# matrix_mixer.net
KiCad netlist of a schematic drawn in EAGLE
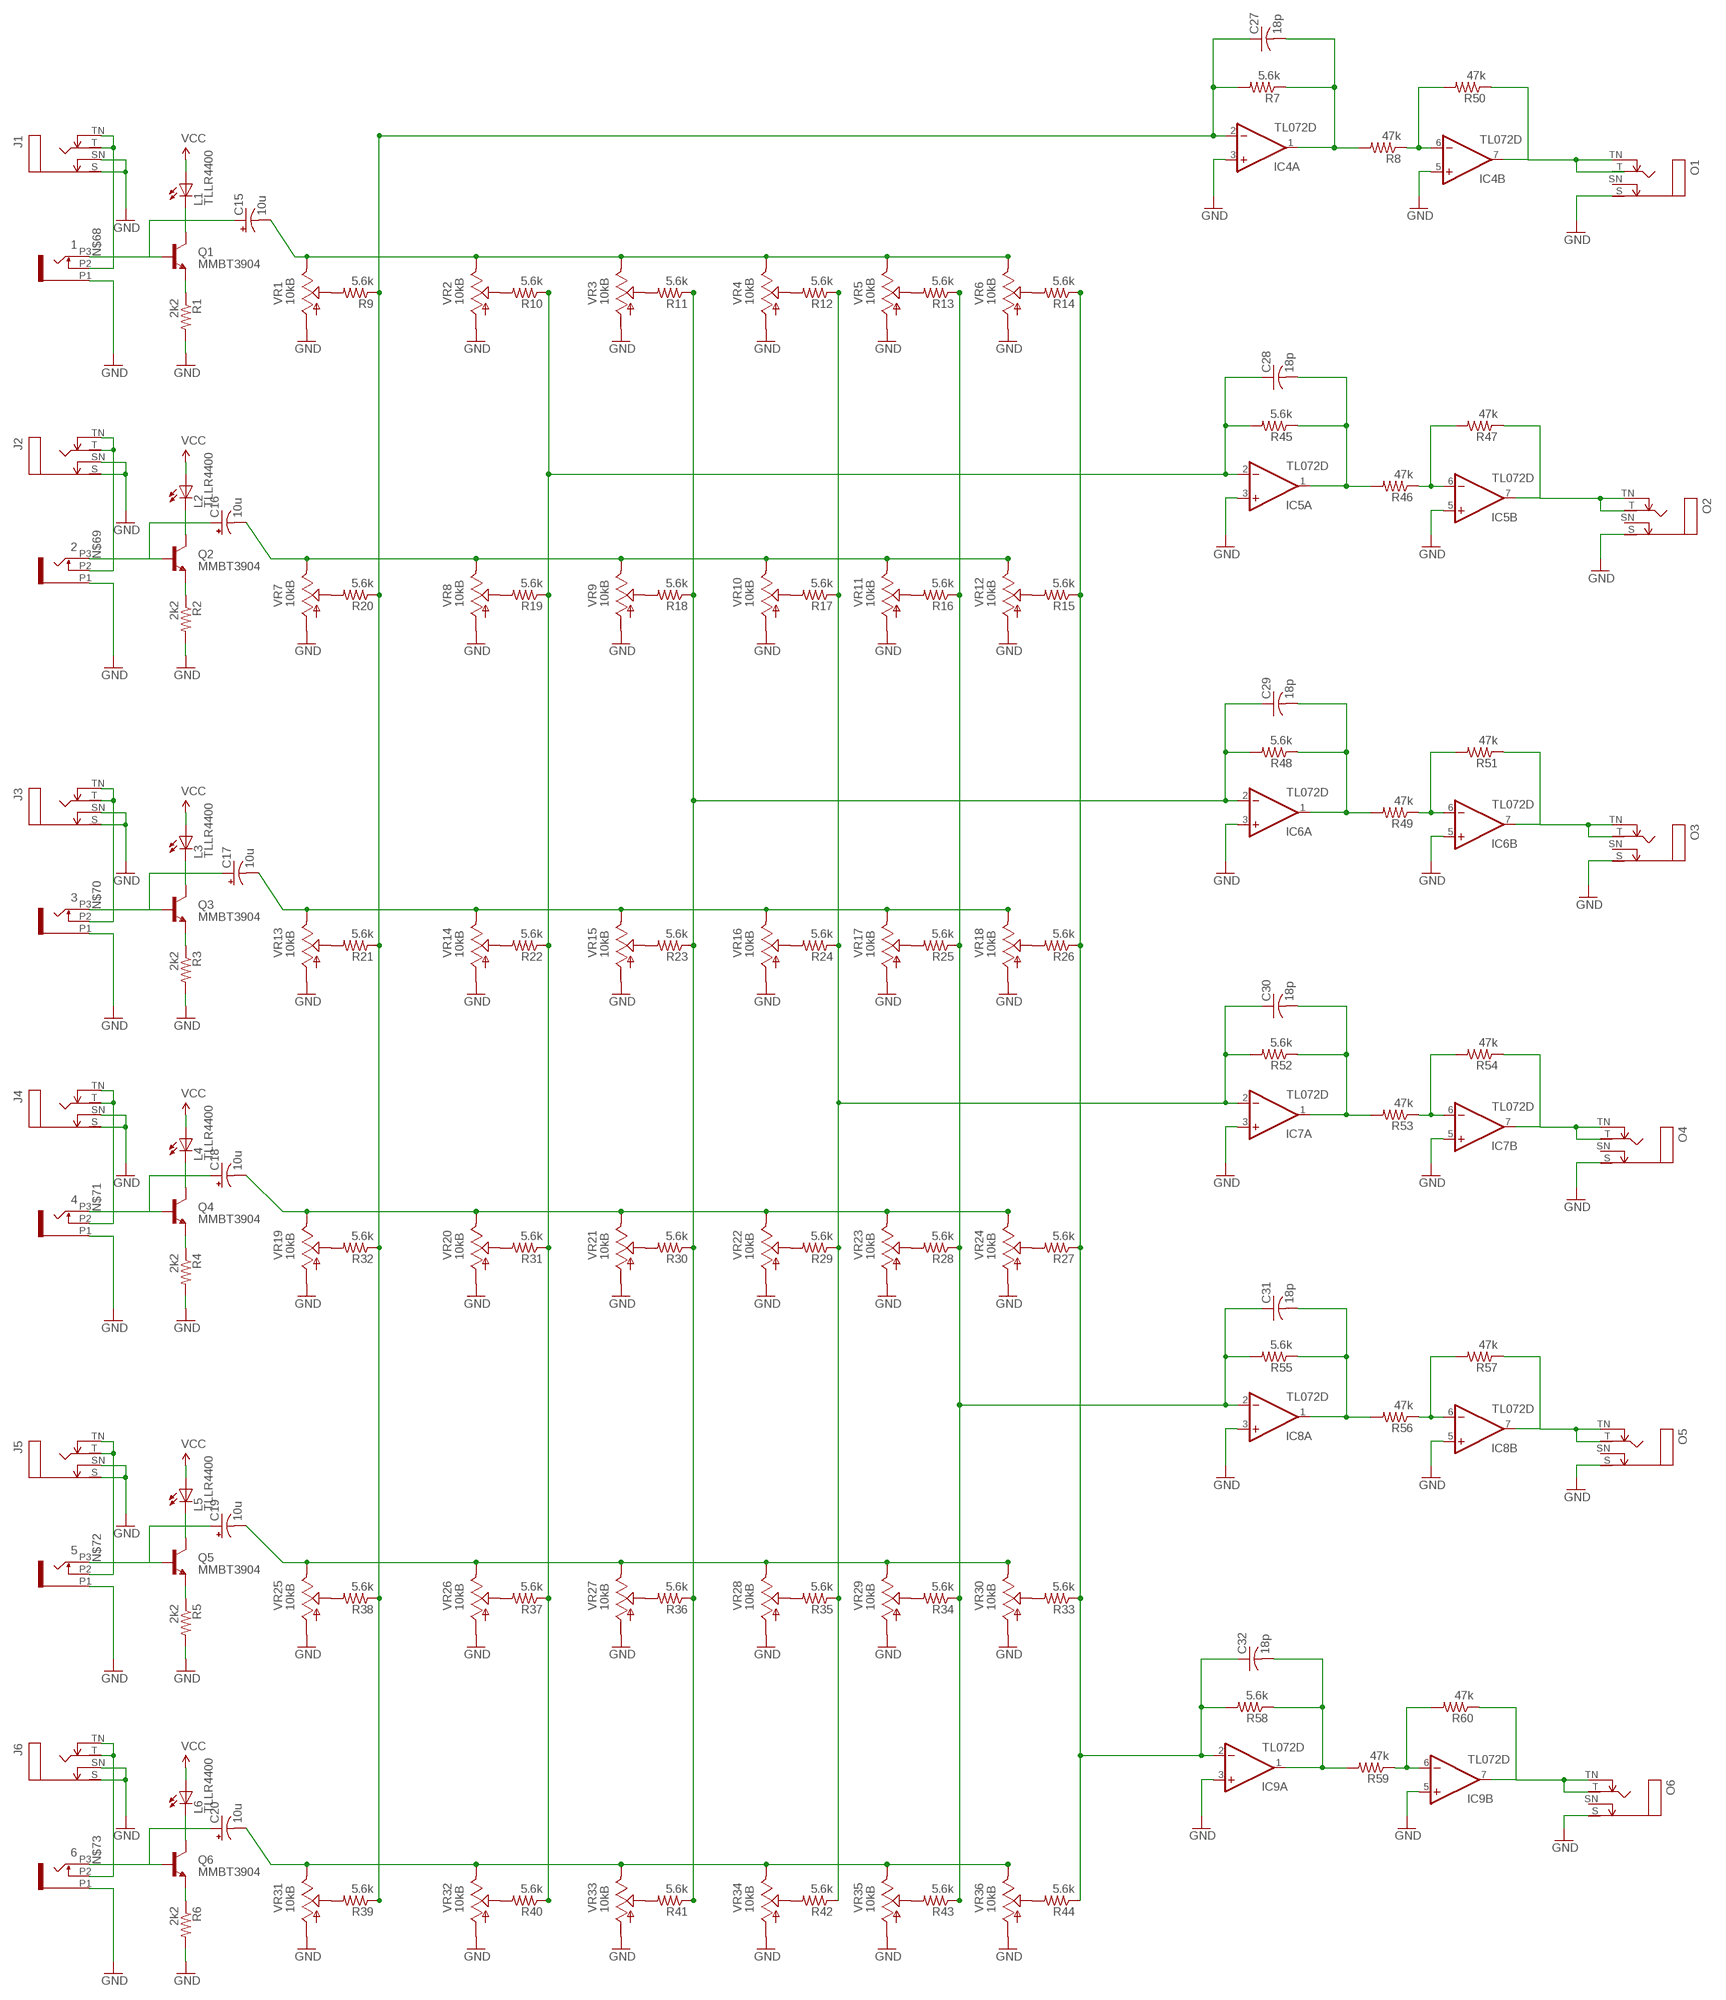
[diagram p0: schematic, sheet 1, part 1 of 2]
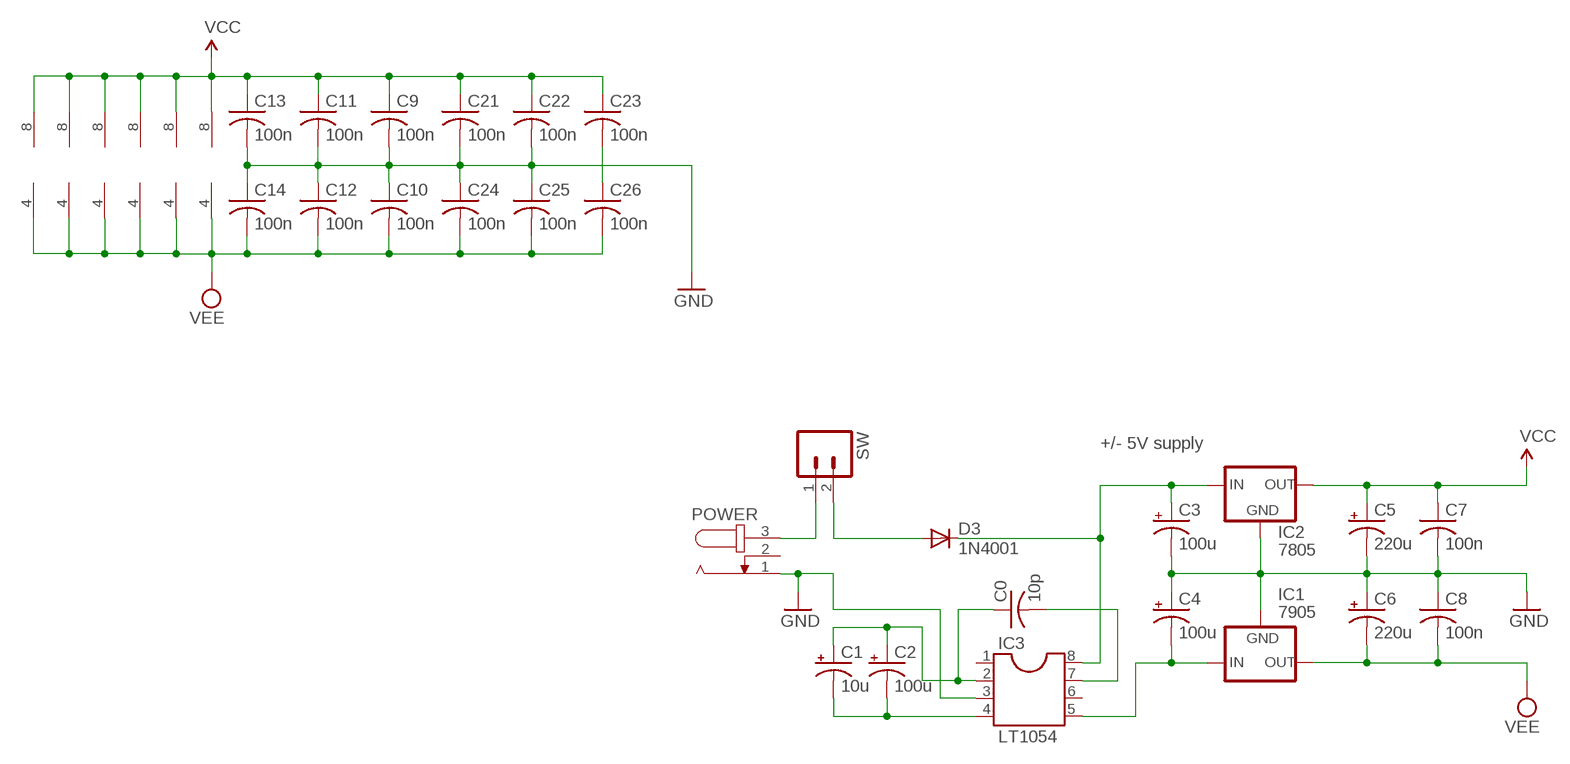
[diagram p1: schematic, sheet 1, part 2 of 2]

(export (version "E")
  (design (tool "Eeschema 10.0.6"))
  (components
    (comp (ref "1")
      (value "PJ301_THONKICONN6")
      (footprint "eagle-import:WQP_PJ_301M6")
      (libsource (lib "eagle-import") (part "PJ301_THONKICONN6"))
    )
    (comp (ref "2")
      (value "PJ301_THONKICONN6")
      (footprint "eagle-import:WQP_PJ_301M6")
      (libsource (lib "eagle-import") (part "PJ301_THONKICONN6"))
    )
    (comp (ref "3")
      (value "PJ301_THONKICONN6")
      (footprint "eagle-import:WQP_PJ_301M6")
      (libsource (lib "eagle-import") (part "PJ301_THONKICONN6"))
    )
    (comp (ref "4")
      (value "PJ301_THONKICONN6")
      (footprint "eagle-import:WQP_PJ_301M6")
      (libsource (lib "eagle-import") (part "PJ301_THONKICONN6"))
    )
    (comp (ref "5")
      (value "PJ301_THONKICONN6")
      (footprint "eagle-import:WQP_PJ_301M6")
      (libsource (lib "eagle-import") (part "PJ301_THONKICONN6"))
    )
    (comp (ref "6")
      (value "PJ301_THONKICONN6")
      (footprint "eagle-import:WQP_PJ_301M6")
      (libsource (lib "eagle-import") (part "PJ301_THONKICONN6"))
    )
    (comp (ref "C0")
      (value "10p")
      (footprint "eagle-import:C025-025X050")
      (libsource (lib "eagle-import") (part "C-US025-025X050"))
    )
    (comp (ref "C1")
      (value "10u")
      (footprint "eagle-import:E2,5-5")
      (libsource (lib "eagle-import") (part "CPOL-USE2.5-5"))
    )
    (comp (ref "C2")
      (value "100u")
      (footprint "eagle-import:E2,5-6")
      (libsource (lib "eagle-import") (part "CPOL-USE2.5-6"))
    )
    (comp (ref "C3")
      (value "100u")
      (footprint "eagle-import:E2,5-7")
      (libsource (lib "eagle-import") (part "CPOL-USE2.5-7"))
    )
    (comp (ref "C4")
      (value "100u")
      (footprint "eagle-import:E2,5-7")
      (libsource (lib "eagle-import") (part "CPOL-USE2.5-7"))
    )
    (comp (ref "C5")
      (value "220u")
      (footprint "eagle-import:E5-10,5")
      (libsource (lib "eagle-import") (part "CPOL-USE5-10.5"))
    )
    (comp (ref "C6")
      (value "220u")
      (footprint "eagle-import:E5-10,5")
      (libsource (lib "eagle-import") (part "CPOL-USE5-10.5"))
    )
    (comp (ref "C7")
      (value "100n")
      (footprint "eagle-import:C025-025X050")
      (libsource (lib "eagle-import") (part "C-US025-025X050"))
    )
    (comp (ref "C8")
      (value "100n")
      (footprint "eagle-import:C025-025X050")
      (libsource (lib "eagle-import") (part "C-US025-025X050"))
    )
    (comp (ref "C9")
      (value "100n")
      (footprint "eagle-import:C0603")
      (libsource (lib "eagle-import") (part "C-USC0603"))
    )
    (comp (ref "C10")
      (value "100n")
      (footprint "eagle-import:C0603")
      (libsource (lib "eagle-import") (part "C-USC0603"))
    )
    (comp (ref "C11")
      (value "100n")
      (footprint "eagle-import:C0603")
      (libsource (lib "eagle-import") (part "C-USC0603"))
    )
    (comp (ref "C12")
      (value "100n")
      (footprint "eagle-import:C0603")
      (libsource (lib "eagle-import") (part "C-USC0603"))
    )
    (comp (ref "C13")
      (value "100n")
      (footprint "eagle-import:C0603")
      (libsource (lib "eagle-import") (part "C-USC0603"))
    )
    (comp (ref "C14")
      (value "100n")
      (footprint "eagle-import:C0603")
      (libsource (lib "eagle-import") (part "C-USC0603"))
    )
    (comp (ref "C15")
      (value "10u")
      (footprint "eagle-import:PANASONIC_B")
      (libsource (lib "eagle-import") (part "CPOL-USB"))
    )
    (comp (ref "C16")
      (value "10u")
      (footprint "eagle-import:PANASONIC_B")
      (libsource (lib "eagle-import") (part "CPOL-USB"))
    )
    (comp (ref "C17")
      (value "10u")
      (footprint "eagle-import:PANASONIC_B")
      (libsource (lib "eagle-import") (part "CPOL-USB"))
    )
    (comp (ref "C18")
      (value "10u")
      (footprint "eagle-import:PANASONIC_B")
      (libsource (lib "eagle-import") (part "CPOL-USB"))
    )
    (comp (ref "C19")
      (value "10u")
      (footprint "eagle-import:PANASONIC_B")
      (libsource (lib "eagle-import") (part "CPOL-USB"))
    )
    (comp (ref "C20")
      (value "10u")
      (footprint "eagle-import:PANASONIC_B")
      (libsource (lib "eagle-import") (part "CPOL-USB"))
    )
    (comp (ref "C21")
      (value "100n")
      (footprint "eagle-import:C0603")
      (libsource (lib "eagle-import") (part "C-USC0603"))
    )
    (comp (ref "C22")
      (value "100n")
      (footprint "eagle-import:C0603")
      (libsource (lib "eagle-import") (part "C-USC0603"))
    )
    (comp (ref "C23")
      (value "100n")
      (footprint "eagle-import:C0603")
      (libsource (lib "eagle-import") (part "C-USC0603"))
    )
    (comp (ref "C24")
      (value "100n")
      (footprint "eagle-import:C0603")
      (libsource (lib "eagle-import") (part "C-USC0603"))
    )
    (comp (ref "C25")
      (value "100n")
      (footprint "eagle-import:C0603")
      (libsource (lib "eagle-import") (part "C-USC0603"))
    )
    (comp (ref "C26")
      (value "100n")
      (footprint "eagle-import:C0603")
      (libsource (lib "eagle-import") (part "C-USC0603"))
    )
    (comp (ref "C27")
      (value "18p")
      (footprint "eagle-import:C0603")
      (libsource (lib "eagle-import") (part "C-USC0603"))
    )
    (comp (ref "C28")
      (value "18p")
      (footprint "eagle-import:C0603")
      (libsource (lib "eagle-import") (part "C-USC0603"))
    )
    (comp (ref "C29")
      (value "18p")
      (footprint "eagle-import:C0603")
      (libsource (lib "eagle-import") (part "C-USC0603"))
    )
    (comp (ref "C30")
      (value "18p")
      (footprint "eagle-import:C0603")
      (libsource (lib "eagle-import") (part "C-USC0603"))
    )
    (comp (ref "C31")
      (value "18p")
      (footprint "eagle-import:C0603")
      (libsource (lib "eagle-import") (part "C-USC0603"))
    )
    (comp (ref "C32")
      (value "18p")
      (footprint "eagle-import:C0603")
      (libsource (lib "eagle-import") (part "C-USC0603"))
    )
    (comp (ref "D3")
      (value "1N4001")
      (footprint "eagle-import:DO41-10")
      (libsource (lib "eagle-import") (part "1N4004"))
    )
    (comp (ref "IC1")
      (value "7905")
      (footprint "eagle-import:79XXS")
      (libsource (lib "eagle-import") (part "79XXS"))
    )
    (comp (ref "IC2")
      (value "7805")
      (footprint "eagle-import:78XXS")
      (libsource (lib "eagle-import") (part "78XXS"))
    )
    (comp (ref "IC3")
      (value "LT1054")
      (footprint "eagle-import:DIL08")
      (libsource (lib "eagle-import") (part "DIL8"))
    )
    (comp (ref "IC4")
      (value "TL072D")
      (footprint "eagle-import:SO08")
      (libsource (lib "eagle-import") (part "TL072D"))
    )
    (comp (ref "IC5")
      (value "TL072D")
      (footprint "eagle-import:SO08")
      (libsource (lib "eagle-import") (part "TL072D"))
    )
    (comp (ref "IC6")
      (value "TL072D")
      (footprint "eagle-import:SO08")
      (libsource (lib "eagle-import") (part "TL072D"))
    )
    (comp (ref "IC7")
      (value "TL072D")
      (footprint "eagle-import:SO08")
      (libsource (lib "eagle-import") (part "TL072D"))
    )
    (comp (ref "IC8")
      (value "TL072D")
      (footprint "eagle-import:SO08")
      (libsource (lib "eagle-import") (part "TL072D"))
    )
    (comp (ref "IC9")
      (value "TL072D")
      (footprint "eagle-import:SO08")
      (libsource (lib "eagle-import") (part "TL072D"))
    )
    (comp (ref "J1")
      (value "MONOSWS")
      (footprint "eagle-import:NMJ4HC-S")
      (libsource (lib "eagle-import") (part "MONOSWS"))
    )
    (comp (ref "J2")
      (value "MONOSWS")
      (footprint "eagle-import:NMJ4HC-S")
      (libsource (lib "eagle-import") (part "MONOSWS"))
    )
    (comp (ref "J3")
      (value "MONOSWS")
      (footprint "eagle-import:NMJ4HC-S")
      (libsource (lib "eagle-import") (part "MONOSWS"))
    )
    (comp (ref "J4")
      (value "MONOSWS")
      (footprint "eagle-import:NMJ4HC-S")
      (libsource (lib "eagle-import") (part "MONOSWS"))
    )
    (comp (ref "J5")
      (value "MONOSWS")
      (footprint "eagle-import:NMJ4HC-S")
      (libsource (lib "eagle-import") (part "MONOSWS"))
    )
    (comp (ref "J6")
      (value "MONOSWS")
      (footprint "eagle-import:NMJ4HC-S")
      (libsource (lib "eagle-import") (part "MONOSWS"))
    )
    (comp (ref "L1")
      (value "TLLR4400")
      (footprint "eagle-import:LED3MM")
      (fields (field (name "MF") "VISHAY SEMICONDUCTOR"))
      (libsource (lib "eagle-import") (part "TLLR4400"))
    )
    (comp (ref "L2")
      (value "TLLR4400")
      (footprint "eagle-import:LED3MM")
      (fields (field (name "MF") "VISHAY SEMICONDUCTOR"))
      (libsource (lib "eagle-import") (part "TLLR4400"))
    )
    (comp (ref "L3")
      (value "TLLR4400")
      (footprint "eagle-import:LED3MM")
      (fields (field (name "MF") "VISHAY SEMICONDUCTOR"))
      (libsource (lib "eagle-import") (part "TLLR4400"))
    )
    (comp (ref "L4")
      (value "TLLR4400")
      (footprint "eagle-import:LED3MM")
      (fields (field (name "MF") "VISHAY SEMICONDUCTOR"))
      (libsource (lib "eagle-import") (part "TLLR4400"))
    )
    (comp (ref "L5")
      (value "TLLR4400")
      (footprint "eagle-import:LED3MM")
      (fields (field (name "MF") "VISHAY SEMICONDUCTOR"))
      (libsource (lib "eagle-import") (part "TLLR4400"))
    )
    (comp (ref "L6")
      (value "TLLR4400")
      (footprint "eagle-import:LED3MM")
      (fields (field (name "MF") "VISHAY SEMICONDUCTOR"))
      (libsource (lib "eagle-import") (part "TLLR4400"))
    )
    (comp (ref "O1")
      (value "MONOSWS")
      (footprint "eagle-import:NMJ4HC-S")
      (libsource (lib "eagle-import") (part "MONOSWS"))
    )
    (comp (ref "O2")
      (value "MONOSWS")
      (footprint "eagle-import:NMJ4HC-S")
      (libsource (lib "eagle-import") (part "MONOSWS"))
    )
    (comp (ref "O3")
      (value "MONOSWS")
      (footprint "eagle-import:NMJ4HC-S")
      (libsource (lib "eagle-import") (part "MONOSWS"))
    )
    (comp (ref "O4")
      (value "MONOSWS")
      (footprint "eagle-import:NMJ4HC-S")
      (libsource (lib "eagle-import") (part "MONOSWS"))
    )
    (comp (ref "O5")
      (value "MONOSWS")
      (footprint "eagle-import:NMJ4HC-S")
      (libsource (lib "eagle-import") (part "MONOSWS"))
    )
    (comp (ref "O6")
      (value "MONOSWS")
      (footprint "eagle-import:NMJ4HC-S")
      (libsource (lib "eagle-import") (part "MONOSWS"))
    )
    (comp (ref "POWER")
      (value "JACK-PLUG2")
      (footprint "eagle-import:SPC4078_BIG_HOLES")
      (libsource (lib "eagle-import") (part "JACK-PLUG2"))
    )
    (comp (ref "Q1")
      (value "MMBT3904")
      (footprint "eagle-import:SOT23-BEC")
      (libsource (lib "eagle-import") (part "-NPN-SOT23-BECMMBT3904LT1"))
    )
    (comp (ref "Q2")
      (value "MMBT3904")
      (footprint "eagle-import:SOT23-BEC")
      (libsource (lib "eagle-import") (part "-NPN-SOT23-BECMMBT3904LT1"))
    )
    (comp (ref "Q3")
      (value "MMBT3904")
      (footprint "eagle-import:SOT23-BEC")
      (libsource (lib "eagle-import") (part "-NPN-SOT23-BECMMBT3904LT1"))
    )
    (comp (ref "Q4")
      (value "MMBT3904")
      (footprint "eagle-import:SOT23-BEC")
      (libsource (lib "eagle-import") (part "-NPN-SOT23-BECMMBT3904LT1"))
    )
    (comp (ref "Q5")
      (value "MMBT3904")
      (footprint "eagle-import:SOT23-BEC")
      (libsource (lib "eagle-import") (part "-NPN-SOT23-BECMMBT3904LT1"))
    )
    (comp (ref "Q6")
      (value "MMBT3904")
      (footprint "eagle-import:SOT23-BEC")
      (libsource (lib "eagle-import") (part "-NPN-SOT23-BECMMBT3904LT1"))
    )
    (comp (ref "R1")
      (value "2k2")
      (footprint "eagle-import:R0603")
      (libsource (lib "eagle-import") (part "R-US_R0603"))
    )
    (comp (ref "R2")
      (value "2k2")
      (footprint "eagle-import:R0603")
      (libsource (lib "eagle-import") (part "R-US_R0603"))
    )
    (comp (ref "R3")
      (value "2k2")
      (footprint "eagle-import:R0603")
      (libsource (lib "eagle-import") (part "R-US_R0603"))
    )
    (comp (ref "R4")
      (value "2k2")
      (footprint "eagle-import:R0603")
      (libsource (lib "eagle-import") (part "R-US_R0603"))
    )
    (comp (ref "R5")
      (value "2k2")
      (footprint "eagle-import:R0603")
      (libsource (lib "eagle-import") (part "R-US_R0603"))
    )
    (comp (ref "R6")
      (value "2k2")
      (footprint "eagle-import:R0603")
      (libsource (lib "eagle-import") (part "R-US_R0603"))
    )
    (comp (ref "R7")
      (value "5.6k")
      (footprint "eagle-import:R0603")
      (libsource (lib "eagle-import") (part "R-US_R0603"))
    )
    (comp (ref "R8")
      (value "47k")
      (footprint "eagle-import:R0603")
      (libsource (lib "eagle-import") (part "R-US_R0603"))
    )
    (comp (ref "R9")
      (value "5.6k")
      (footprint "eagle-import:R0603")
      (libsource (lib "eagle-import") (part "R-US_R0603"))
    )
    (comp (ref "R10")
      (value "5.6k")
      (footprint "eagle-import:R0603")
      (libsource (lib "eagle-import") (part "R-US_R0603"))
    )
    (comp (ref "R11")
      (value "5.6k")
      (footprint "eagle-import:R0603")
      (libsource (lib "eagle-import") (part "R-US_R0603"))
    )
    (comp (ref "R12")
      (value "5.6k")
      (footprint "eagle-import:R0603")
      (libsource (lib "eagle-import") (part "R-US_R0603"))
    )
    (comp (ref "R13")
      (value "5.6k")
      (footprint "eagle-import:R0603")
      (libsource (lib "eagle-import") (part "R-US_R0603"))
    )
    (comp (ref "R14")
      (value "5.6k")
      (footprint "eagle-import:R0603")
      (libsource (lib "eagle-import") (part "R-US_R0603"))
    )
    (comp (ref "R15")
      (value "5.6k")
      (footprint "eagle-import:R0603")
      (libsource (lib "eagle-import") (part "R-US_R0603"))
    )
    (comp (ref "R16")
      (value "5.6k")
      (footprint "eagle-import:R0603")
      (libsource (lib "eagle-import") (part "R-US_R0603"))
    )
    (comp (ref "R17")
      (value "5.6k")
      (footprint "eagle-import:R0603")
      (libsource (lib "eagle-import") (part "R-US_R0603"))
    )
    (comp (ref "R18")
      (value "5.6k")
      (footprint "eagle-import:R0603")
      (libsource (lib "eagle-import") (part "R-US_R0603"))
    )
    (comp (ref "R19")
      (value "5.6k")
      (footprint "eagle-import:R0603")
      (libsource (lib "eagle-import") (part "R-US_R0603"))
    )
    (comp (ref "R20")
      (value "5.6k")
      (footprint "eagle-import:R0603")
      (libsource (lib "eagle-import") (part "R-US_R0603"))
    )
    (comp (ref "R21")
      (value "5.6k")
      (footprint "eagle-import:R0603")
      (libsource (lib "eagle-import") (part "R-US_R0603"))
    )
    (comp (ref "R22")
      (value "5.6k")
      (footprint "eagle-import:R0603")
      (libsource (lib "eagle-import") (part "R-US_R0603"))
    )
    (comp (ref "R23")
      (value "5.6k")
      (footprint "eagle-import:R0603")
      (libsource (lib "eagle-import") (part "R-US_R0603"))
    )
    (comp (ref "R24")
      (value "5.6k")
      (footprint "eagle-import:R0603")
      (libsource (lib "eagle-import") (part "R-US_R0603"))
    )
    (comp (ref "R25")
      (value "5.6k")
      (footprint "eagle-import:R0603")
      (libsource (lib "eagle-import") (part "R-US_R0603"))
    )
    (comp (ref "R26")
      (value "5.6k")
      (footprint "eagle-import:R0603")
      (libsource (lib "eagle-import") (part "R-US_R0603"))
    )
    (comp (ref "R27")
      (value "5.6k")
      (footprint "eagle-import:R0603")
      (libsource (lib "eagle-import") (part "R-US_R0603"))
    )
    (comp (ref "R28")
      (value "5.6k")
      (footprint "eagle-import:R0603")
      (libsource (lib "eagle-import") (part "R-US_R0603"))
    )
    (comp (ref "R29")
      (value "5.6k")
      (footprint "eagle-import:R0603")
      (libsource (lib "eagle-import") (part "R-US_R0603"))
    )
    (comp (ref "R30")
      (value "5.6k")
      (footprint "eagle-import:R0603")
      (libsource (lib "eagle-import") (part "R-US_R0603"))
    )
    (comp (ref "R31")
      (value "5.6k")
      (footprint "eagle-import:R0603")
      (libsource (lib "eagle-import") (part "R-US_R0603"))
    )
    (comp (ref "R32")
      (value "5.6k")
      (footprint "eagle-import:R0603")
      (libsource (lib "eagle-import") (part "R-US_R0603"))
    )
    (comp (ref "R33")
      (value "5.6k")
      (footprint "eagle-import:R0603")
      (libsource (lib "eagle-import") (part "R-US_R0603"))
    )
    (comp (ref "R34")
      (value "5.6k")
      (footprint "eagle-import:R0603")
      (libsource (lib "eagle-import") (part "R-US_R0603"))
    )
    (comp (ref "R35")
      (value "5.6k")
      (footprint "eagle-import:R0603")
      (libsource (lib "eagle-import") (part "R-US_R0603"))
    )
    (comp (ref "R36")
      (value "5.6k")
      (footprint "eagle-import:R0603")
      (libsource (lib "eagle-import") (part "R-US_R0603"))
    )
    (comp (ref "R37")
      (value "5.6k")
      (footprint "eagle-import:R0603")
      (libsource (lib "eagle-import") (part "R-US_R0603"))
    )
    (comp (ref "R38")
      (value "5.6k")
      (footprint "eagle-import:R0603")
      (libsource (lib "eagle-import") (part "R-US_R0603"))
    )
    (comp (ref "R39")
      (value "5.6k")
      (footprint "eagle-import:R0603")
      (libsource (lib "eagle-import") (part "R-US_R0603"))
    )
    (comp (ref "R40")
      (value "5.6k")
      (footprint "eagle-import:R0603")
      (libsource (lib "eagle-import") (part "R-US_R0603"))
    )
    (comp (ref "R41")
      (value "5.6k")
      (footprint "eagle-import:R0603")
      (libsource (lib "eagle-import") (part "R-US_R0603"))
    )
    (comp (ref "R42")
      (value "5.6k")
      (footprint "eagle-import:R0603")
      (libsource (lib "eagle-import") (part "R-US_R0603"))
    )
    (comp (ref "R43")
      (value "5.6k")
      (footprint "eagle-import:R0603")
      (libsource (lib "eagle-import") (part "R-US_R0603"))
    )
    (comp (ref "R44")
      (value "5.6k")
      (footprint "eagle-import:R0603")
      (libsource (lib "eagle-import") (part "R-US_R0603"))
    )
    (comp (ref "R45")
      (value "5.6k")
      (footprint "eagle-import:R0603")
      (libsource (lib "eagle-import") (part "R-US_R0603"))
    )
    (comp (ref "R46")
      (value "47k")
      (footprint "eagle-import:R0603")
      (libsource (lib "eagle-import") (part "R-US_R0603"))
    )
    (comp (ref "R47")
      (value "47k")
      (footprint "eagle-import:R0603")
      (libsource (lib "eagle-import") (part "R-US_R0603"))
    )
    (comp (ref "R48")
      (value "5.6k")
      (footprint "eagle-import:R0603")
      (libsource (lib "eagle-import") (part "R-US_R0603"))
    )
    (comp (ref "R49")
      (value "47k")
      (footprint "eagle-import:R0603")
      (libsource (lib "eagle-import") (part "R-US_R0603"))
    )
    (comp (ref "R50")
      (value "47k")
      (footprint "eagle-import:R0603")
      (libsource (lib "eagle-import") (part "R-US_R0603"))
    )
    (comp (ref "R51")
      (value "47k")
      (footprint "eagle-import:R0603")
      (libsource (lib "eagle-import") (part "R-US_R0603"))
    )
    (comp (ref "R52")
      (value "5.6k")
      (footprint "eagle-import:R0603")
      (libsource (lib "eagle-import") (part "R-US_R0603"))
    )
    (comp (ref "R53")
      (value "47k")
      (footprint "eagle-import:R0603")
      (libsource (lib "eagle-import") (part "R-US_R0603"))
    )
    (comp (ref "R54")
      (value "47k")
      (footprint "eagle-import:R0603")
      (libsource (lib "eagle-import") (part "R-US_R0603"))
    )
    (comp (ref "R55")
      (value "5.6k")
      (footprint "eagle-import:R0603")
      (libsource (lib "eagle-import") (part "R-US_R0603"))
    )
    (comp (ref "R56")
      (value "47k")
      (footprint "eagle-import:R0603")
      (libsource (lib "eagle-import") (part "R-US_R0603"))
    )
    (comp (ref "R57")
      (value "47k")
      (footprint "eagle-import:R0603")
      (libsource (lib "eagle-import") (part "R-US_R0603"))
    )
    (comp (ref "R58")
      (value "5.6k")
      (footprint "eagle-import:R0603")
      (libsource (lib "eagle-import") (part "R-US_R0603"))
    )
    (comp (ref "R59")
      (value "47k")
      (footprint "eagle-import:R0603")
      (libsource (lib "eagle-import") (part "R-US_R0603"))
    )
    (comp (ref "R60")
      (value "47k")
      (footprint "eagle-import:R0603")
      (libsource (lib "eagle-import") (part "R-US_R0603"))
    )
    (comp (ref "SW")
      (value "M02PTH")
      (footprint "eagle-import:1X02")
      (libsource (lib "eagle-import") (part "M02PTH"))
    )
    (comp (ref "VR1")
      (value "10kB")
      (footprint "eagle-import:ALPS_POT_VERTICAL_PS")
      (libsource (lib "eagle-import") (part "POT_USVERTICAL_PS"))
    )
    (comp (ref "VR2")
      (value "10kB")
      (footprint "eagle-import:ALPS_POT_VERTICAL_PS")
      (libsource (lib "eagle-import") (part "POT_USVERTICAL_PS"))
    )
    (comp (ref "VR3")
      (value "10kB")
      (footprint "eagle-import:ALPS_POT_VERTICAL_PS")
      (libsource (lib "eagle-import") (part "POT_USVERTICAL_PS"))
    )
    (comp (ref "VR4")
      (value "10kB")
      (footprint "eagle-import:ALPS_POT_VERTICAL_PS")
      (libsource (lib "eagle-import") (part "POT_USVERTICAL_PS"))
    )
    (comp (ref "VR5")
      (value "10kB")
      (footprint "eagle-import:ALPS_POT_VERTICAL_PS")
      (libsource (lib "eagle-import") (part "POT_USVERTICAL_PS"))
    )
    (comp (ref "VR6")
      (value "10kB")
      (footprint "eagle-import:ALPS_POT_VERTICAL_PS")
      (libsource (lib "eagle-import") (part "POT_USVERTICAL_PS"))
    )
    (comp (ref "VR7")
      (value "10kB")
      (footprint "eagle-import:ALPS_POT_VERTICAL_PS")
      (libsource (lib "eagle-import") (part "POT_USVERTICAL_PS"))
    )
    (comp (ref "VR8")
      (value "10kB")
      (footprint "eagle-import:ALPS_POT_VERTICAL_PS")
      (libsource (lib "eagle-import") (part "POT_USVERTICAL_PS"))
    )
    (comp (ref "VR9")
      (value "10kB")
      (footprint "eagle-import:ALPS_POT_VERTICAL_PS")
      (libsource (lib "eagle-import") (part "POT_USVERTICAL_PS"))
    )
    (comp (ref "VR10")
      (value "10kB")
      (footprint "eagle-import:ALPS_POT_VERTICAL_PS")
      (libsource (lib "eagle-import") (part "POT_USVERTICAL_PS"))
    )
    (comp (ref "VR11")
      (value "10kB")
      (footprint "eagle-import:ALPS_POT_VERTICAL_PS")
      (libsource (lib "eagle-import") (part "POT_USVERTICAL_PS"))
    )
    (comp (ref "VR12")
      (value "10kB")
      (footprint "eagle-import:ALPS_POT_VERTICAL_PS")
      (libsource (lib "eagle-import") (part "POT_USVERTICAL_PS"))
    )
    (comp (ref "VR13")
      (value "10kB")
      (footprint "eagle-import:ALPS_POT_VERTICAL_PS")
      (libsource (lib "eagle-import") (part "POT_USVERTICAL_PS"))
    )
    (comp (ref "VR14")
      (value "10kB")
      (footprint "eagle-import:ALPS_POT_VERTICAL_PS")
      (libsource (lib "eagle-import") (part "POT_USVERTICAL_PS"))
    )
    (comp (ref "VR15")
      (value "10kB")
      (footprint "eagle-import:ALPS_POT_VERTICAL_PS")
      (libsource (lib "eagle-import") (part "POT_USVERTICAL_PS"))
    )
    (comp (ref "VR16")
      (value "10kB")
      (footprint "eagle-import:ALPS_POT_VERTICAL_PS")
      (libsource (lib "eagle-import") (part "POT_USVERTICAL_PS"))
    )
    (comp (ref "VR17")
      (value "10kB")
      (footprint "eagle-import:ALPS_POT_VERTICAL_PS")
      (libsource (lib "eagle-import") (part "POT_USVERTICAL_PS"))
    )
    (comp (ref "VR18")
      (value "10kB")
      (footprint "eagle-import:ALPS_POT_VERTICAL_PS")
      (libsource (lib "eagle-import") (part "POT_USVERTICAL_PS"))
    )
    (comp (ref "VR19")
      (value "10kB")
      (footprint "eagle-import:ALPS_POT_VERTICAL_PS")
      (libsource (lib "eagle-import") (part "POT_USVERTICAL_PS"))
    )
    (comp (ref "VR20")
      (value "10kB")
      (footprint "eagle-import:ALPS_POT_VERTICAL_PS")
      (libsource (lib "eagle-import") (part "POT_USVERTICAL_PS"))
    )
    (comp (ref "VR21")
      (value "10kB")
      (footprint "eagle-import:ALPS_POT_VERTICAL_PS")
      (libsource (lib "eagle-import") (part "POT_USVERTICAL_PS"))
    )
    (comp (ref "VR22")
      (value "10kB")
      (footprint "eagle-import:ALPS_POT_VERTICAL_PS")
      (libsource (lib "eagle-import") (part "POT_USVERTICAL_PS"))
    )
    (comp (ref "VR23")
      (value "10kB")
      (footprint "eagle-import:ALPS_POT_VERTICAL_PS")
      (libsource (lib "eagle-import") (part "POT_USVERTICAL_PS"))
    )
    (comp (ref "VR24")
      (value "10kB")
      (footprint "eagle-import:ALPS_POT_VERTICAL_PS")
      (libsource (lib "eagle-import") (part "POT_USVERTICAL_PS"))
    )
    (comp (ref "VR25")
      (value "10kB")
      (footprint "eagle-import:ALPS_POT_VERTICAL_PS")
      (libsource (lib "eagle-import") (part "POT_USVERTICAL_PS"))
    )
    (comp (ref "VR26")
      (value "10kB")
      (footprint "eagle-import:ALPS_POT_VERTICAL_PS")
      (libsource (lib "eagle-import") (part "POT_USVERTICAL_PS"))
    )
    (comp (ref "VR27")
      (value "10kB")
      (footprint "eagle-import:ALPS_POT_VERTICAL_PS")
      (libsource (lib "eagle-import") (part "POT_USVERTICAL_PS"))
    )
    (comp (ref "VR28")
      (value "10kB")
      (footprint "eagle-import:ALPS_POT_VERTICAL_PS")
      (libsource (lib "eagle-import") (part "POT_USVERTICAL_PS"))
    )
    (comp (ref "VR29")
      (value "10kB")
      (footprint "eagle-import:ALPS_POT_VERTICAL_PS")
      (libsource (lib "eagle-import") (part "POT_USVERTICAL_PS"))
    )
    (comp (ref "VR30")
      (value "10kB")
      (footprint "eagle-import:ALPS_POT_VERTICAL_PS")
      (libsource (lib "eagle-import") (part "POT_USVERTICAL_PS"))
    )
    (comp (ref "VR31")
      (value "10kB")
      (footprint "eagle-import:ALPS_POT_VERTICAL_PS")
      (libsource (lib "eagle-import") (part "POT_USVERTICAL_PS"))
    )
    (comp (ref "VR32")
      (value "10kB")
      (footprint "eagle-import:ALPS_POT_VERTICAL_PS")
      (libsource (lib "eagle-import") (part "POT_USVERTICAL_PS"))
    )
    (comp (ref "VR33")
      (value "10kB")
      (footprint "eagle-import:ALPS_POT_VERTICAL_PS")
      (libsource (lib "eagle-import") (part "POT_USVERTICAL_PS"))
    )
    (comp (ref "VR34")
      (value "10kB")
      (footprint "eagle-import:ALPS_POT_VERTICAL_PS")
      (libsource (lib "eagle-import") (part "POT_USVERTICAL_PS"))
    )
    (comp (ref "VR35")
      (value "10kB")
      (footprint "eagle-import:ALPS_POT_VERTICAL_PS")
      (libsource (lib "eagle-import") (part "POT_USVERTICAL_PS"))
    )
    (comp (ref "VR36")
      (value "10kB")
      (footprint "eagle-import:ALPS_POT_VERTICAL_PS")
      (libsource (lib "eagle-import") (part "POT_USVERTICAL_PS"))
    )
  )
  (nets
    (net (code "1") (name "/N$68") (class "Default")
      (node (ref "1") (pin "P3") (pinfunction "3_P3") (pintype "passive"))
      (node (ref "C15") (pin "+") (pinfunction "+_+") (pintype "passive"))
      (node (ref "Q1") (pin "B") (pinfunction "B_B") (pintype "passive"))
    )
    (net (code "2") (name "/N$69") (class "Default")
      (node (ref "2") (pin "P3") (pinfunction "3_P3") (pintype "passive"))
      (node (ref "C16") (pin "+") (pinfunction "+_+") (pintype "passive"))
      (node (ref "Q2") (pin "B") (pinfunction "B_B") (pintype "passive"))
    )
    (net (code "3") (name "/N$70") (class "Default")
      (node (ref "3") (pin "P3") (pinfunction "3_P3") (pintype "passive"))
      (node (ref "C17") (pin "+") (pinfunction "+_+") (pintype "passive"))
      (node (ref "Q3") (pin "B") (pinfunction "B_B") (pintype "passive"))
    )
    (net (code "4") (name "/N$71") (class "Default")
      (node (ref "4") (pin "P3") (pinfunction "3_P3") (pintype "passive"))
      (node (ref "C18") (pin "+") (pinfunction "+_+") (pintype "passive"))
      (node (ref "Q4") (pin "B") (pinfunction "B_B") (pintype "passive"))
    )
    (net (code "5") (name "/N$72") (class "Default")
      (node (ref "5") (pin "P3") (pinfunction "3_P3") (pintype "passive"))
      (node (ref "C19") (pin "+") (pinfunction "+_+") (pintype "passive"))
      (node (ref "Q5") (pin "B") (pinfunction "B_B") (pintype "passive"))
    )
    (net (code "6") (name "/N$73") (class "Default")
      (node (ref "6") (pin "P3") (pinfunction "3_P3") (pintype "passive"))
      (node (ref "C20") (pin "+") (pinfunction "+_+") (pintype "passive"))
      (node (ref "Q6") (pin "B") (pinfunction "B_B") (pintype "passive"))
    )
    (net (code "7") (name "GND") (class "Default")
      (node (ref "1") (pin "P1") (pinfunction "1_P1") (pintype "passive"))
      (node (ref "2") (pin "P1") (pinfunction "1_P1") (pintype "passive"))
      (node (ref "3") (pin "P1") (pinfunction "1_P1") (pintype "passive"))
      (node (ref "4") (pin "P1") (pinfunction "1_P1") (pintype "passive"))
      (node (ref "5") (pin "P1") (pinfunction "1_P1") (pintype "passive"))
      (node (ref "6") (pin "P1") (pinfunction "1_P1") (pintype "passive"))
      (node (ref "C10") (pin "1") (pinfunction "1_1") (pintype "passive"))
      (node (ref "C11") (pin "2") (pinfunction "2_2") (pintype "passive"))
      (node (ref "C12") (pin "1") (pinfunction "1_1") (pintype "passive"))
      (node (ref "C13") (pin "2") (pinfunction "2_2") (pintype "passive"))
      (node (ref "C14") (pin "1") (pinfunction "1_1") (pintype "passive"))
      (node (ref "C21") (pin "2") (pinfunction "2_2") (pintype "passive"))
      (node (ref "C22") (pin "2") (pinfunction "2_2") (pintype "passive"))
      (node (ref "C23") (pin "2") (pinfunction "2_2") (pintype "passive"))
      (node (ref "C24") (pin "1") (pinfunction "1_1") (pintype "passive"))
      (node (ref "C25") (pin "1") (pinfunction "1_1") (pintype "passive"))
      (node (ref "C26") (pin "1") (pinfunction "1_1") (pintype "passive"))
      (node (ref "C3") (pin "-") (pinfunction "-_-") (pintype "passive"))
      (node (ref "C4") (pin "+") (pinfunction "+_+") (pintype "passive"))
      (node (ref "C5") (pin "-") (pinfunction "-_-") (pintype "passive"))
      (node (ref "C6") (pin "+") (pinfunction "+_+") (pintype "passive"))
      (node (ref "C7") (pin "2") (pinfunction "2_2") (pintype "passive"))
      (node (ref "C8") (pin "1") (pinfunction "1_1") (pintype "passive"))
      (node (ref "C9") (pin "2") (pinfunction "2_2") (pintype "passive"))
      (node (ref "IC1") (pin "GND") (pinfunction "GND_GND") (pintype "input"))
      (node (ref "IC2") (pin "GND") (pinfunction "GND_GND") (pintype "input"))
      (node (ref "IC3") (pin "3") (pinfunction "3_3") (pintype "passive"))
      (node (ref "IC4") (pin "3") (pinfunction "+IN_3") (pintype "input"))
      (node (ref "IC4") (pin "5") (pinfunction "+IN_5") (pintype "input"))
      (node (ref "IC5") (pin "3") (pinfunction "+IN_3") (pintype "input"))
      (node (ref "IC5") (pin "5") (pinfunction "+IN_5") (pintype "input"))
      (node (ref "IC6") (pin "3") (pinfunction "+IN_3") (pintype "input"))
      (node (ref "IC6") (pin "5") (pinfunction "+IN_5") (pintype "input"))
      (node (ref "IC7") (pin "3") (pinfunction "+IN_3") (pintype "input"))
      (node (ref "IC7") (pin "5") (pinfunction "+IN_5") (pintype "input"))
      (node (ref "IC8") (pin "3") (pinfunction "+IN_3") (pintype "input"))
      (node (ref "IC8") (pin "5") (pinfunction "+IN_5") (pintype "input"))
      (node (ref "IC9") (pin "3") (pinfunction "+IN_3") (pintype "input"))
      (node (ref "IC9") (pin "5") (pinfunction "+IN_5") (pintype "input"))
      (node (ref "J1") (pin "S") (pinfunction "S_S") (pintype "passive"))
      (node (ref "J1") (pin "SN") (pinfunction "SN_SN") (pintype "passive"))
      (node (ref "J2") (pin "S") (pinfunction "S_S") (pintype "passive"))
      (node (ref "J2") (pin "SN") (pinfunction "SN_SN") (pintype "passive"))
      (node (ref "J3") (pin "S") (pinfunction "S_S") (pintype "passive"))
      (node (ref "J3") (pin "SN") (pinfunction "SN_SN") (pintype "passive"))
      (node (ref "J4") (pin "S") (pinfunction "S_S") (pintype "passive"))
      (node (ref "J4") (pin "SN") (pinfunction "SN_SN") (pintype "passive"))
      (node (ref "J5") (pin "S") (pinfunction "S_S") (pintype "passive"))
      (node (ref "J5") (pin "SN") (pinfunction "SN_SN") (pintype "passive"))
      (node (ref "J6") (pin "S") (pinfunction "S_S") (pintype "passive"))
      (node (ref "J6") (pin "SN") (pinfunction "SN_SN") (pintype "passive"))
      (node (ref "O1") (pin "S") (pinfunction "S_S") (pintype "passive"))
      (node (ref "O2") (pin "S") (pinfunction "S_S") (pintype "passive"))
      (node (ref "O3") (pin "S") (pinfunction "S_S") (pintype "passive"))
      (node (ref "O4") (pin "S") (pinfunction "S_S") (pintype "passive"))
      (node (ref "O5") (pin "S") (pinfunction "S_S") (pintype "passive"))
      (node (ref "O6") (pin "S") (pinfunction "S_S") (pintype "passive"))
      (node (ref "POWER") (pin "1") (pinfunction "1_1") (pintype "passive"))
      (node (ref "R1") (pin "2") (pinfunction "2_2") (pintype "passive"))
      (node (ref "R2") (pin "2") (pinfunction "2_2") (pintype "passive"))
      (node (ref "R3") (pin "2") (pinfunction "2_2") (pintype "passive"))
      (node (ref "R4") (pin "2") (pinfunction "2_2") (pintype "passive"))
      (node (ref "R5") (pin "2") (pinfunction "2_2") (pintype "passive"))
      (node (ref "R6") (pin "2") (pinfunction "2_2") (pintype "passive"))
      (node (ref "VR1") (pin "P$3") (pinfunction "A_P$3") (pintype "passive"))
      (node (ref "VR10") (pin "P$3") (pinfunction "A_P$3") (pintype "passive"))
      (node (ref "VR11") (pin "P$3") (pinfunction "A_P$3") (pintype "passive"))
      (node (ref "VR12") (pin "P$3") (pinfunction "A_P$3") (pintype "passive"))
      (node (ref "VR13") (pin "P$3") (pinfunction "A_P$3") (pintype "passive"))
      (node (ref "VR14") (pin "P$3") (pinfunction "A_P$3") (pintype "passive"))
      (node (ref "VR15") (pin "P$3") (pinfunction "A_P$3") (pintype "passive"))
      (node (ref "VR16") (pin "P$3") (pinfunction "A_P$3") (pintype "passive"))
      (node (ref "VR17") (pin "P$3") (pinfunction "A_P$3") (pintype "passive"))
      (node (ref "VR18") (pin "P$3") (pinfunction "A_P$3") (pintype "passive"))
      (node (ref "VR19") (pin "P$3") (pinfunction "A_P$3") (pintype "passive"))
      (node (ref "VR2") (pin "P$3") (pinfunction "A_P$3") (pintype "passive"))
      (node (ref "VR20") (pin "P$3") (pinfunction "A_P$3") (pintype "passive"))
      (node (ref "VR21") (pin "P$3") (pinfunction "A_P$3") (pintype "passive"))
      (node (ref "VR22") (pin "P$3") (pinfunction "A_P$3") (pintype "passive"))
      (node (ref "VR23") (pin "P$3") (pinfunction "A_P$3") (pintype "passive"))
      (node (ref "VR24") (pin "P$3") (pinfunction "A_P$3") (pintype "passive"))
      (node (ref "VR25") (pin "P$3") (pinfunction "A_P$3") (pintype "passive"))
      (node (ref "VR26") (pin "P$3") (pinfunction "A_P$3") (pintype "passive"))
      (node (ref "VR27") (pin "P$3") (pinfunction "A_P$3") (pintype "passive"))
      (node (ref "VR28") (pin "P$3") (pinfunction "A_P$3") (pintype "passive"))
      (node (ref "VR29") (pin "P$3") (pinfunction "A_P$3") (pintype "passive"))
      (node (ref "VR3") (pin "P$3") (pinfunction "A_P$3") (pintype "passive"))
      (node (ref "VR30") (pin "P$3") (pinfunction "A_P$3") (pintype "passive"))
      (node (ref "VR31") (pin "P$3") (pinfunction "A_P$3") (pintype "passive"))
      (node (ref "VR32") (pin "P$3") (pinfunction "A_P$3") (pintype "passive"))
      (node (ref "VR33") (pin "P$3") (pinfunction "A_P$3") (pintype "passive"))
      (node (ref "VR34") (pin "P$3") (pinfunction "A_P$3") (pintype "passive"))
      (node (ref "VR35") (pin "P$3") (pinfunction "A_P$3") (pintype "passive"))
      (node (ref "VR36") (pin "P$3") (pinfunction "A_P$3") (pintype "passive"))
      (node (ref "VR4") (pin "P$3") (pinfunction "A_P$3") (pintype "passive"))
      (node (ref "VR5") (pin "P$3") (pinfunction "A_P$3") (pintype "passive"))
      (node (ref "VR6") (pin "P$3") (pinfunction "A_P$3") (pintype "passive"))
      (node (ref "VR7") (pin "P$3") (pinfunction "A_P$3") (pintype "passive"))
      (node (ref "VR8") (pin "P$3") (pinfunction "A_P$3") (pintype "passive"))
      (node (ref "VR9") (pin "P$3") (pinfunction "A_P$3") (pintype "passive"))
    )
    (net (code "8") (name "Net-(1-2)") (class "Default")
      (node (ref "1") (pin "P2") (pinfunction "2_P2") (pintype "passive"))
      (node (ref "J1") (pin "T") (pinfunction "T_T") (pintype "passive"))
      (node (ref "J1") (pin "TN") (pinfunction "TN_TN") (pintype "passive"))
    )
    (net (code "9") (name "Net-(2-2)") (class "Default")
      (node (ref "2") (pin "P2") (pinfunction "2_P2") (pintype "passive"))
      (node (ref "J2") (pin "T") (pinfunction "T_T") (pintype "passive"))
      (node (ref "J2") (pin "TN") (pinfunction "TN_TN") (pintype "passive"))
    )
    (net (code "10") (name "Net-(3-2)") (class "Default")
      (node (ref "3") (pin "P2") (pinfunction "2_P2") (pintype "passive"))
      (node (ref "J3") (pin "T") (pinfunction "T_T") (pintype "passive"))
      (node (ref "J3") (pin "TN") (pinfunction "TN_TN") (pintype "passive"))
    )
    (net (code "11") (name "Net-(4-2)") (class "Default")
      (node (ref "4") (pin "P2") (pinfunction "2_P2") (pintype "passive"))
      (node (ref "J4") (pin "T") (pinfunction "T_T") (pintype "passive"))
      (node (ref "J4") (pin "TN") (pinfunction "TN_TN") (pintype "passive"))
    )
    (net (code "12") (name "Net-(5-2)") (class "Default")
      (node (ref "5") (pin "P2") (pinfunction "2_P2") (pintype "passive"))
      (node (ref "J5") (pin "T") (pinfunction "T_T") (pintype "passive"))
      (node (ref "J5") (pin "TN") (pinfunction "TN_TN") (pintype "passive"))
    )
    (net (code "13") (name "Net-(6-2)") (class "Default")
      (node (ref "6") (pin "P2") (pinfunction "2_P2") (pintype "passive"))
      (node (ref "J6") (pin "T") (pinfunction "T_T") (pintype "passive"))
      (node (ref "J6") (pin "TN") (pinfunction "TN_TN") (pintype "passive"))
    )
    (net (code "14") (name "Net-(C0-Pad1)") (class "Default")
      (node (ref "C0") (pin "1") (pinfunction "1_1") (pintype "passive"))
      (node (ref "C1") (pin "+") (pinfunction "+_+") (pintype "passive"))
      (node (ref "C2") (pin "+") (pinfunction "+_+") (pintype "passive"))
      (node (ref "IC3") (pin "2") (pinfunction "2_2") (pintype "passive"))
    )
    (net (code "15") (name "Net-(C0-Pad2)") (class "Default")
      (node (ref "C0") (pin "2") (pinfunction "2_2") (pintype "passive"))
      (node (ref "IC3") (pin "7") (pinfunction "7_7") (pintype "passive"))
    )
    (net (code "16") (name "Net-(C1-Pad-)") (class "Default")
      (node (ref "C1") (pin "-") (pinfunction "-_-") (pintype "passive"))
      (node (ref "C2") (pin "-") (pinfunction "-_-") (pintype "passive"))
      (node (ref "IC3") (pin "4") (pinfunction "4_4") (pintype "passive"))
    )
    (net (code "17") (name "Net-(C3-Pad+)") (class "Default")
      (node (ref "C3") (pin "+") (pinfunction "+_+") (pintype "passive"))
      (node (ref "D3") (pin "C") (pinfunction "C_C") (pintype "passive"))
      (node (ref "IC2") (pin "IN") (pinfunction "IN_IN") (pintype "input"))
      (node (ref "IC3") (pin "8") (pinfunction "8_8") (pintype "passive"))
    )
    (net (code "18") (name "Net-(C4-Pad-)") (class "Default")
      (node (ref "C4") (pin "-") (pinfunction "-_-") (pintype "passive"))
      (node (ref "IC1") (pin "IN") (pinfunction "IN_IN") (pintype "input"))
      (node (ref "IC3") (pin "5") (pinfunction "5_5") (pintype "passive"))
    )
    (net (code "19") (name "Net-(D3-PadA)") (class "Default")
      (node (ref "D3") (pin "A") (pinfunction "A_A") (pintype "passive"))
      (node (ref "SW") (pin "2") (pinfunction "2_2") (pintype "passive"))
    )
    (net (code "20") (name "Net-(IC4A--IN)") (class "Default")
      (node (ref "C27") (pin "1") (pinfunction "1_1") (pintype "passive"))
      (node (ref "IC4") (pin "2") (pinfunction "-IN_2") (pintype "input"))
      (node (ref "R20") (pin "1") (pinfunction "1_1") (pintype "passive"))
      (node (ref "R21") (pin "1") (pinfunction "1_1") (pintype "passive"))
      (node (ref "R32") (pin "1") (pinfunction "1_1") (pintype "passive"))
      (node (ref "R38") (pin "1") (pinfunction "1_1") (pintype "passive"))
      (node (ref "R39") (pin "1") (pinfunction "1_1") (pintype "passive"))
      (node (ref "R7") (pin "2") (pinfunction "2_2") (pintype "passive"))
      (node (ref "R9") (pin "1") (pinfunction "1_1") (pintype "passive"))
    )
    (net (code "21") (name "Net-(IC4A-OUT)") (class "Default")
      (node (ref "C27") (pin "2") (pinfunction "2_2") (pintype "passive"))
      (node (ref "IC4") (pin "1") (pinfunction "OUT_1") (pintype "output"))
      (node (ref "R7") (pin "1") (pinfunction "1_1") (pintype "passive"))
      (node (ref "R8") (pin "2") (pinfunction "2_2") (pintype "passive"))
    )
    (net (code "22") (name "Net-(IC4B--IN)") (class "Default")
      (node (ref "IC4") (pin "6") (pinfunction "-IN_6") (pintype "input"))
      (node (ref "R50") (pin "2") (pinfunction "2_2") (pintype "passive"))
      (node (ref "R8") (pin "1") (pinfunction "1_1") (pintype "passive"))
    )
    (net (code "23") (name "Net-(IC4B-OUT)") (class "Default")
      (node (ref "IC4") (pin "7") (pinfunction "OUT_7") (pintype "output"))
      (node (ref "O1") (pin "TN") (pinfunction "TN_TN") (pintype "passive"))
      (node (ref "R50") (pin "1") (pinfunction "1_1") (pintype "passive"))
    )
    (net (code "24") (name "Net-(IC5A--IN)") (class "Default")
      (node (ref "C28") (pin "1") (pinfunction "1_1") (pintype "passive"))
      (node (ref "IC5") (pin "2") (pinfunction "-IN_2") (pintype "input"))
      (node (ref "R10") (pin "1") (pinfunction "1_1") (pintype "passive"))
      (node (ref "R19") (pin "1") (pinfunction "1_1") (pintype "passive"))
      (node (ref "R22") (pin "1") (pinfunction "1_1") (pintype "passive"))
      (node (ref "R31") (pin "1") (pinfunction "1_1") (pintype "passive"))
      (node (ref "R37") (pin "1") (pinfunction "1_1") (pintype "passive"))
      (node (ref "R40") (pin "1") (pinfunction "1_1") (pintype "passive"))
      (node (ref "R45") (pin "2") (pinfunction "2_2") (pintype "passive"))
    )
    (net (code "25") (name "Net-(IC5A-OUT)") (class "Default")
      (node (ref "C28") (pin "2") (pinfunction "2_2") (pintype "passive"))
      (node (ref "IC5") (pin "1") (pinfunction "OUT_1") (pintype "output"))
      (node (ref "R45") (pin "1") (pinfunction "1_1") (pintype "passive"))
      (node (ref "R46") (pin "2") (pinfunction "2_2") (pintype "passive"))
    )
    (net (code "26") (name "Net-(IC5B--IN)") (class "Default")
      (node (ref "IC5") (pin "6") (pinfunction "-IN_6") (pintype "input"))
      (node (ref "R46") (pin "1") (pinfunction "1_1") (pintype "passive"))
      (node (ref "R47") (pin "2") (pinfunction "2_2") (pintype "passive"))
    )
    (net (code "27") (name "Net-(IC5B-OUT)") (class "Default")
      (node (ref "IC5") (pin "7") (pinfunction "OUT_7") (pintype "output"))
      (node (ref "O2") (pin "T") (pinfunction "T_T") (pintype "passive"))
      (node (ref "O2") (pin "TN") (pinfunction "TN_TN") (pintype "passive"))
      (node (ref "R47") (pin "1") (pinfunction "1_1") (pintype "passive"))
    )
    (net (code "28") (name "Net-(IC6A--IN)") (class "Default")
      (node (ref "C29") (pin "1") (pinfunction "1_1") (pintype "passive"))
      (node (ref "IC6") (pin "2") (pinfunction "-IN_2") (pintype "input"))
      (node (ref "R11") (pin "1") (pinfunction "1_1") (pintype "passive"))
      (node (ref "R18") (pin "1") (pinfunction "1_1") (pintype "passive"))
      (node (ref "R23") (pin "1") (pinfunction "1_1") (pintype "passive"))
      (node (ref "R30") (pin "1") (pinfunction "1_1") (pintype "passive"))
      (node (ref "R36") (pin "1") (pinfunction "1_1") (pintype "passive"))
      (node (ref "R41") (pin "1") (pinfunction "1_1") (pintype "passive"))
      (node (ref "R48") (pin "2") (pinfunction "2_2") (pintype "passive"))
    )
    (net (code "29") (name "Net-(IC6A-OUT)") (class "Default")
      (node (ref "C29") (pin "2") (pinfunction "2_2") (pintype "passive"))
      (node (ref "IC6") (pin "1") (pinfunction "OUT_1") (pintype "output"))
      (node (ref "R48") (pin "1") (pinfunction "1_1") (pintype "passive"))
      (node (ref "R49") (pin "2") (pinfunction "2_2") (pintype "passive"))
    )
    (net (code "30") (name "Net-(IC6B--IN)") (class "Default")
      (node (ref "IC6") (pin "6") (pinfunction "-IN_6") (pintype "input"))
      (node (ref "R49") (pin "1") (pinfunction "1_1") (pintype "passive"))
      (node (ref "R51") (pin "2") (pinfunction "2_2") (pintype "passive"))
    )
    (net (code "31") (name "Net-(IC6B-OUT)") (class "Default")
      (node (ref "IC6") (pin "7") (pinfunction "OUT_7") (pintype "output"))
      (node (ref "O3") (pin "T") (pinfunction "T_T") (pintype "passive"))
      (node (ref "O3") (pin "TN") (pinfunction "TN_TN") (pintype "passive"))
      (node (ref "R51") (pin "1") (pinfunction "1_1") (pintype "passive"))
    )
    (net (code "32") (name "Net-(IC7A--IN)") (class "Default")
      (node (ref "C30") (pin "1") (pinfunction "1_1") (pintype "passive"))
      (node (ref "IC7") (pin "2") (pinfunction "-IN_2") (pintype "input"))
      (node (ref "R12") (pin "1") (pinfunction "1_1") (pintype "passive"))
      (node (ref "R17") (pin "1") (pinfunction "1_1") (pintype "passive"))
      (node (ref "R24") (pin "1") (pinfunction "1_1") (pintype "passive"))
      (node (ref "R29") (pin "1") (pinfunction "1_1") (pintype "passive"))
      (node (ref "R35") (pin "1") (pinfunction "1_1") (pintype "passive"))
      (node (ref "R42") (pin "1") (pinfunction "1_1") (pintype "passive"))
      (node (ref "R52") (pin "2") (pinfunction "2_2") (pintype "passive"))
    )
    (net (code "33") (name "Net-(IC7A-OUT)") (class "Default")
      (node (ref "C30") (pin "2") (pinfunction "2_2") (pintype "passive"))
      (node (ref "IC7") (pin "1") (pinfunction "OUT_1") (pintype "output"))
      (node (ref "R52") (pin "1") (pinfunction "1_1") (pintype "passive"))
      (node (ref "R53") (pin "2") (pinfunction "2_2") (pintype "passive"))
    )
    (net (code "34") (name "Net-(IC7B--IN)") (class "Default")
      (node (ref "IC7") (pin "6") (pinfunction "-IN_6") (pintype "input"))
      (node (ref "R53") (pin "1") (pinfunction "1_1") (pintype "passive"))
      (node (ref "R54") (pin "2") (pinfunction "2_2") (pintype "passive"))
    )
    (net (code "35") (name "Net-(IC7B-OUT)") (class "Default")
      (node (ref "IC7") (pin "7") (pinfunction "OUT_7") (pintype "output"))
      (node (ref "O4") (pin "T") (pinfunction "T_T") (pintype "passive"))
      (node (ref "O4") (pin "TN") (pinfunction "TN_TN") (pintype "passive"))
      (node (ref "R54") (pin "1") (pinfunction "1_1") (pintype "passive"))
    )
    (net (code "36") (name "Net-(IC8A--IN)") (class "Default")
      (node (ref "C31") (pin "1") (pinfunction "1_1") (pintype "passive"))
      (node (ref "IC8") (pin "2") (pinfunction "-IN_2") (pintype "input"))
      (node (ref "R13") (pin "1") (pinfunction "1_1") (pintype "passive"))
      (node (ref "R16") (pin "1") (pinfunction "1_1") (pintype "passive"))
      (node (ref "R25") (pin "1") (pinfunction "1_1") (pintype "passive"))
      (node (ref "R28") (pin "1") (pinfunction "1_1") (pintype "passive"))
      (node (ref "R34") (pin "1") (pinfunction "1_1") (pintype "passive"))
      (node (ref "R43") (pin "1") (pinfunction "1_1") (pintype "passive"))
      (node (ref "R55") (pin "2") (pinfunction "2_2") (pintype "passive"))
    )
    (net (code "37") (name "Net-(IC8A-OUT)") (class "Default")
      (node (ref "C31") (pin "2") (pinfunction "2_2") (pintype "passive"))
      (node (ref "IC8") (pin "1") (pinfunction "OUT_1") (pintype "output"))
      (node (ref "R55") (pin "1") (pinfunction "1_1") (pintype "passive"))
      (node (ref "R56") (pin "2") (pinfunction "2_2") (pintype "passive"))
    )
    (net (code "38") (name "Net-(IC8B--IN)") (class "Default")
      (node (ref "IC8") (pin "6") (pinfunction "-IN_6") (pintype "input"))
      (node (ref "R56") (pin "1") (pinfunction "1_1") (pintype "passive"))
      (node (ref "R57") (pin "2") (pinfunction "2_2") (pintype "passive"))
    )
    (net (code "39") (name "Net-(IC8B-OUT)") (class "Default")
      (node (ref "IC8") (pin "7") (pinfunction "OUT_7") (pintype "output"))
      (node (ref "O5") (pin "T") (pinfunction "T_T") (pintype "passive"))
      (node (ref "O5") (pin "TN") (pinfunction "TN_TN") (pintype "passive"))
      (node (ref "R57") (pin "1") (pinfunction "1_1") (pintype "passive"))
    )
    (net (code "40") (name "Net-(IC9A--IN)") (class "Default")
      (node (ref "C32") (pin "1") (pinfunction "1_1") (pintype "passive"))
      (node (ref "IC9") (pin "2") (pinfunction "-IN_2") (pintype "input"))
      (node (ref "R14") (pin "1") (pinfunction "1_1") (pintype "passive"))
      (node (ref "R15") (pin "1") (pinfunction "1_1") (pintype "passive"))
      (node (ref "R26") (pin "1") (pinfunction "1_1") (pintype "passive"))
      (node (ref "R27") (pin "1") (pinfunction "1_1") (pintype "passive"))
      (node (ref "R33") (pin "1") (pinfunction "1_1") (pintype "passive"))
      (node (ref "R44") (pin "1") (pinfunction "1_1") (pintype "passive"))
      (node (ref "R58") (pin "2") (pinfunction "2_2") (pintype "passive"))
    )
    (net (code "41") (name "Net-(IC9A-OUT)") (class "Default")
      (node (ref "C32") (pin "2") (pinfunction "2_2") (pintype "passive"))
      (node (ref "IC9") (pin "1") (pinfunction "OUT_1") (pintype "output"))
      (node (ref "R58") (pin "1") (pinfunction "1_1") (pintype "passive"))
      (node (ref "R59") (pin "2") (pinfunction "2_2") (pintype "passive"))
    )
    (net (code "42") (name "Net-(IC9B--IN)") (class "Default")
      (node (ref "IC9") (pin "6") (pinfunction "-IN_6") (pintype "input"))
      (node (ref "R59") (pin "1") (pinfunction "1_1") (pintype "passive"))
      (node (ref "R60") (pin "2") (pinfunction "2_2") (pintype "passive"))
    )
    (net (code "43") (name "Net-(IC9B-OUT)") (class "Default")
      (node (ref "IC9") (pin "7") (pinfunction "OUT_7") (pintype "output"))
      (node (ref "O6") (pin "T") (pinfunction "T_T") (pintype "passive"))
      (node (ref "O6") (pin "TN") (pinfunction "TN_TN") (pintype "passive"))
      (node (ref "R60") (pin "1") (pinfunction "1_1") (pintype "passive"))
    )
    (net (code "44") (name "Net-(L1-C)") (class "Default")
      (node (ref "L1") (pin "K") (pinfunction "C_K") (pintype "passive"))
      (node (ref "Q1") (pin "C") (pinfunction "C_C") (pintype "passive"))
    )
    (net (code "45") (name "Net-(L2-C)") (class "Default")
      (node (ref "L2") (pin "K") (pinfunction "C_K") (pintype "passive"))
      (node (ref "Q2") (pin "C") (pinfunction "C_C") (pintype "passive"))
    )
    (net (code "46") (name "Net-(L3-C)") (class "Default")
      (node (ref "L3") (pin "K") (pinfunction "C_K") (pintype "passive"))
      (node (ref "Q3") (pin "C") (pinfunction "C_C") (pintype "passive"))
    )
    (net (code "47") (name "Net-(L4-C)") (class "Default")
      (node (ref "L4") (pin "K") (pinfunction "C_K") (pintype "passive"))
      (node (ref "Q4") (pin "C") (pinfunction "C_C") (pintype "passive"))
    )
    (net (code "48") (name "Net-(L5-C)") (class "Default")
      (node (ref "L5") (pin "K") (pinfunction "C_K") (pintype "passive"))
      (node (ref "Q5") (pin "C") (pinfunction "C_C") (pintype "passive"))
    )
    (net (code "49") (name "Net-(L6-C)") (class "Default")
      (node (ref "L6") (pin "K") (pinfunction "C_K") (pintype "passive"))
      (node (ref "Q6") (pin "C") (pinfunction "C_C") (pintype "passive"))
    )
    (net (code "50") (name "Net-(POWER-Pad3)") (class "Default")
      (node (ref "POWER") (pin "3") (pinfunction "3_3") (pintype "passive"))
      (node (ref "SW") (pin "1") (pinfunction "1_1") (pintype "passive"))
    )
    (net (code "51") (name "Net-(Q1-PadE)") (class "Default")
      (node (ref "Q1") (pin "E") (pinfunction "E_E") (pintype "passive"))
      (node (ref "R1") (pin "1") (pinfunction "1_1") (pintype "passive"))
    )
    (net (code "52") (name "Net-(Q2-PadE)") (class "Default")
      (node (ref "Q2") (pin "E") (pinfunction "E_E") (pintype "passive"))
      (node (ref "R2") (pin "1") (pinfunction "1_1") (pintype "passive"))
    )
    (net (code "53") (name "Net-(Q3-PadE)") (class "Default")
      (node (ref "Q3") (pin "E") (pinfunction "E_E") (pintype "passive"))
      (node (ref "R3") (pin "1") (pinfunction "1_1") (pintype "passive"))
    )
    (net (code "54") (name "Net-(Q4-PadE)") (class "Default")
      (node (ref "Q4") (pin "E") (pinfunction "E_E") (pintype "passive"))
      (node (ref "R4") (pin "1") (pinfunction "1_1") (pintype "passive"))
    )
    (net (code "55") (name "Net-(Q5-PadE)") (class "Default")
      (node (ref "Q5") (pin "E") (pinfunction "E_E") (pintype "passive"))
      (node (ref "R5") (pin "1") (pinfunction "1_1") (pintype "passive"))
    )
    (net (code "56") (name "Net-(Q6-PadE)") (class "Default")
      (node (ref "Q6") (pin "E") (pinfunction "E_E") (pintype "passive"))
      (node (ref "R6") (pin "1") (pinfunction "1_1") (pintype "passive"))
    )
    (net (code "57") (name "Net-(VR1-E)") (class "Default")
      (node (ref "C15") (pin "-") (pinfunction "-_-") (pintype "passive"))
      (node (ref "VR1") (pin "P$1") (pinfunction "E_P$1") (pintype "passive"))
      (node (ref "VR2") (pin "P$1") (pinfunction "E_P$1") (pintype "passive"))
      (node (ref "VR3") (pin "P$1") (pinfunction "E_P$1") (pintype "passive"))
      (node (ref "VR4") (pin "P$1") (pinfunction "E_P$1") (pintype "passive"))
      (node (ref "VR5") (pin "P$1") (pinfunction "E_P$1") (pintype "passive"))
      (node (ref "VR6") (pin "P$1") (pinfunction "E_P$1") (pintype "passive"))
    )
    (net (code "58") (name "Net-(VR1-S)") (class "Default")
      (node (ref "R9") (pin "2") (pinfunction "2_2") (pintype "passive"))
      (node (ref "VR1") (pin "P$2") (pinfunction "S_P$2") (pintype "passive"))
    )
    (net (code "59") (name "Net-(VR2-S)") (class "Default")
      (node (ref "R10") (pin "2") (pinfunction "2_2") (pintype "passive"))
      (node (ref "VR2") (pin "P$2") (pinfunction "S_P$2") (pintype "passive"))
    )
    (net (code "60") (name "Net-(VR3-S)") (class "Default")
      (node (ref "R11") (pin "2") (pinfunction "2_2") (pintype "passive"))
      (node (ref "VR3") (pin "P$2") (pinfunction "S_P$2") (pintype "passive"))
    )
    (net (code "61") (name "Net-(VR4-S)") (class "Default")
      (node (ref "R12") (pin "2") (pinfunction "2_2") (pintype "passive"))
      (node (ref "VR4") (pin "P$2") (pinfunction "S_P$2") (pintype "passive"))
    )
    (net (code "62") (name "Net-(VR5-S)") (class "Default")
      (node (ref "R13") (pin "2") (pinfunction "2_2") (pintype "passive"))
      (node (ref "VR5") (pin "P$2") (pinfunction "S_P$2") (pintype "passive"))
    )
    (net (code "63") (name "Net-(VR6-S)") (class "Default")
      (node (ref "R14") (pin "2") (pinfunction "2_2") (pintype "passive"))
      (node (ref "VR6") (pin "P$2") (pinfunction "S_P$2") (pintype "passive"))
    )
    (net (code "64") (name "Net-(VR7-S)") (class "Default")
      (node (ref "R20") (pin "2") (pinfunction "2_2") (pintype "passive"))
      (node (ref "VR7") (pin "P$2") (pinfunction "S_P$2") (pintype "passive"))
    )
    (net (code "65") (name "Net-(VR8-S)") (class "Default")
      (node (ref "R19") (pin "2") (pinfunction "2_2") (pintype "passive"))
      (node (ref "VR8") (pin "P$2") (pinfunction "S_P$2") (pintype "passive"))
    )
    (net (code "66") (name "Net-(VR9-S)") (class "Default")
      (node (ref "R18") (pin "2") (pinfunction "2_2") (pintype "passive"))
      (node (ref "VR9") (pin "P$2") (pinfunction "S_P$2") (pintype "passive"))
    )
    (net (code "67") (name "Net-(VR10-E)") (class "Default")
      (node (ref "C16") (pin "-") (pinfunction "-_-") (pintype "passive"))
      (node (ref "VR10") (pin "P$1") (pinfunction "E_P$1") (pintype "passive"))
      (node (ref "VR11") (pin "P$1") (pinfunction "E_P$1") (pintype "passive"))
      (node (ref "VR12") (pin "P$1") (pinfunction "E_P$1") (pintype "passive"))
      (node (ref "VR7") (pin "P$1") (pinfunction "E_P$1") (pintype "passive"))
      (node (ref "VR8") (pin "P$1") (pinfunction "E_P$1") (pintype "passive"))
      (node (ref "VR9") (pin "P$1") (pinfunction "E_P$1") (pintype "passive"))
    )
    (net (code "68") (name "Net-(VR10-S)") (class "Default")
      (node (ref "R17") (pin "2") (pinfunction "2_2") (pintype "passive"))
      (node (ref "VR10") (pin "P$2") (pinfunction "S_P$2") (pintype "passive"))
    )
    (net (code "69") (name "Net-(VR11-S)") (class "Default")
      (node (ref "R16") (pin "2") (pinfunction "2_2") (pintype "passive"))
      (node (ref "VR11") (pin "P$2") (pinfunction "S_P$2") (pintype "passive"))
    )
    (net (code "70") (name "Net-(VR12-S)") (class "Default")
      (node (ref "R15") (pin "2") (pinfunction "2_2") (pintype "passive"))
      (node (ref "VR12") (pin "P$2") (pinfunction "S_P$2") (pintype "passive"))
    )
    (net (code "71") (name "Net-(VR13-E)") (class "Default")
      (node (ref "C17") (pin "-") (pinfunction "-_-") (pintype "passive"))
      (node (ref "VR13") (pin "P$1") (pinfunction "E_P$1") (pintype "passive"))
      (node (ref "VR14") (pin "P$1") (pinfunction "E_P$1") (pintype "passive"))
      (node (ref "VR15") (pin "P$1") (pinfunction "E_P$1") (pintype "passive"))
      (node (ref "VR16") (pin "P$1") (pinfunction "E_P$1") (pintype "passive"))
      (node (ref "VR17") (pin "P$1") (pinfunction "E_P$1") (pintype "passive"))
      (node (ref "VR18") (pin "P$1") (pinfunction "E_P$1") (pintype "passive"))
    )
    (net (code "72") (name "Net-(VR13-S)") (class "Default")
      (node (ref "R21") (pin "2") (pinfunction "2_2") (pintype "passive"))
      (node (ref "VR13") (pin "P$2") (pinfunction "S_P$2") (pintype "passive"))
    )
    (net (code "73") (name "Net-(VR14-S)") (class "Default")
      (node (ref "R22") (pin "2") (pinfunction "2_2") (pintype "passive"))
      (node (ref "VR14") (pin "P$2") (pinfunction "S_P$2") (pintype "passive"))
    )
    (net (code "74") (name "Net-(VR15-S)") (class "Default")
      (node (ref "R23") (pin "2") (pinfunction "2_2") (pintype "passive"))
      (node (ref "VR15") (pin "P$2") (pinfunction "S_P$2") (pintype "passive"))
    )
    (net (code "75") (name "Net-(VR16-S)") (class "Default")
      (node (ref "R24") (pin "2") (pinfunction "2_2") (pintype "passive"))
      (node (ref "VR16") (pin "P$2") (pinfunction "S_P$2") (pintype "passive"))
    )
    (net (code "76") (name "Net-(VR17-S)") (class "Default")
      (node (ref "R25") (pin "2") (pinfunction "2_2") (pintype "passive"))
      (node (ref "VR17") (pin "P$2") (pinfunction "S_P$2") (pintype "passive"))
    )
    (net (code "77") (name "Net-(VR18-S)") (class "Default")
      (node (ref "R26") (pin "2") (pinfunction "2_2") (pintype "passive"))
      (node (ref "VR18") (pin "P$2") (pinfunction "S_P$2") (pintype "passive"))
    )
    (net (code "78") (name "Net-(VR19-E)") (class "Default")
      (node (ref "C18") (pin "-") (pinfunction "-_-") (pintype "passive"))
      (node (ref "VR19") (pin "P$1") (pinfunction "E_P$1") (pintype "passive"))
      (node (ref "VR20") (pin "P$1") (pinfunction "E_P$1") (pintype "passive"))
      (node (ref "VR21") (pin "P$1") (pinfunction "E_P$1") (pintype "passive"))
      (node (ref "VR22") (pin "P$1") (pinfunction "E_P$1") (pintype "passive"))
      (node (ref "VR23") (pin "P$1") (pinfunction "E_P$1") (pintype "passive"))
      (node (ref "VR24") (pin "P$1") (pinfunction "E_P$1") (pintype "passive"))
    )
    (net (code "79") (name "Net-(VR19-S)") (class "Default")
      (node (ref "R32") (pin "2") (pinfunction "2_2") (pintype "passive"))
      (node (ref "VR19") (pin "P$2") (pinfunction "S_P$2") (pintype "passive"))
    )
    (net (code "80") (name "Net-(VR20-S)") (class "Default")
      (node (ref "R31") (pin "2") (pinfunction "2_2") (pintype "passive"))
      (node (ref "VR20") (pin "P$2") (pinfunction "S_P$2") (pintype "passive"))
    )
    (net (code "81") (name "Net-(VR21-S)") (class "Default")
      (node (ref "R30") (pin "2") (pinfunction "2_2") (pintype "passive"))
      (node (ref "VR21") (pin "P$2") (pinfunction "S_P$2") (pintype "passive"))
    )
    (net (code "82") (name "Net-(VR22-S)") (class "Default")
      (node (ref "R29") (pin "2") (pinfunction "2_2") (pintype "passive"))
      (node (ref "VR22") (pin "P$2") (pinfunction "S_P$2") (pintype "passive"))
    )
    (net (code "83") (name "Net-(VR23-S)") (class "Default")
      (node (ref "R28") (pin "2") (pinfunction "2_2") (pintype "passive"))
      (node (ref "VR23") (pin "P$2") (pinfunction "S_P$2") (pintype "passive"))
    )
    (net (code "84") (name "Net-(VR24-S)") (class "Default")
      (node (ref "R27") (pin "2") (pinfunction "2_2") (pintype "passive"))
      (node (ref "VR24") (pin "P$2") (pinfunction "S_P$2") (pintype "passive"))
    )
    (net (code "85") (name "Net-(VR25-E)") (class "Default")
      (node (ref "C19") (pin "-") (pinfunction "-_-") (pintype "passive"))
      (node (ref "VR25") (pin "P$1") (pinfunction "E_P$1") (pintype "passive"))
      (node (ref "VR26") (pin "P$1") (pinfunction "E_P$1") (pintype "passive"))
      (node (ref "VR27") (pin "P$1") (pinfunction "E_P$1") (pintype "passive"))
      (node (ref "VR28") (pin "P$1") (pinfunction "E_P$1") (pintype "passive"))
      (node (ref "VR29") (pin "P$1") (pinfunction "E_P$1") (pintype "passive"))
      (node (ref "VR30") (pin "P$1") (pinfunction "E_P$1") (pintype "passive"))
    )
    (net (code "86") (name "Net-(VR25-S)") (class "Default")
      (node (ref "R38") (pin "2") (pinfunction "2_2") (pintype "passive"))
      (node (ref "VR25") (pin "P$2") (pinfunction "S_P$2") (pintype "passive"))
    )
    (net (code "87") (name "Net-(VR26-S)") (class "Default")
      (node (ref "R37") (pin "2") (pinfunction "2_2") (pintype "passive"))
      (node (ref "VR26") (pin "P$2") (pinfunction "S_P$2") (pintype "passive"))
    )
    (net (code "88") (name "Net-(VR27-S)") (class "Default")
      (node (ref "R36") (pin "2") (pinfunction "2_2") (pintype "passive"))
      (node (ref "VR27") (pin "P$2") (pinfunction "S_P$2") (pintype "passive"))
    )
    (net (code "89") (name "Net-(VR28-S)") (class "Default")
      (node (ref "R35") (pin "2") (pinfunction "2_2") (pintype "passive"))
      (node (ref "VR28") (pin "P$2") (pinfunction "S_P$2") (pintype "passive"))
    )
    (net (code "90") (name "Net-(VR29-S)") (class "Default")
      (node (ref "R34") (pin "2") (pinfunction "2_2") (pintype "passive"))
      (node (ref "VR29") (pin "P$2") (pinfunction "S_P$2") (pintype "passive"))
    )
    (net (code "91") (name "Net-(VR30-S)") (class "Default")
      (node (ref "R33") (pin "2") (pinfunction "2_2") (pintype "passive"))
      (node (ref "VR30") (pin "P$2") (pinfunction "S_P$2") (pintype "passive"))
    )
    (net (code "92") (name "Net-(VR31-E)") (class "Default")
      (node (ref "C20") (pin "-") (pinfunction "-_-") (pintype "passive"))
      (node (ref "VR31") (pin "P$1") (pinfunction "E_P$1") (pintype "passive"))
      (node (ref "VR32") (pin "P$1") (pinfunction "E_P$1") (pintype "passive"))
      (node (ref "VR33") (pin "P$1") (pinfunction "E_P$1") (pintype "passive"))
      (node (ref "VR34") (pin "P$1") (pinfunction "E_P$1") (pintype "passive"))
      (node (ref "VR35") (pin "P$1") (pinfunction "E_P$1") (pintype "passive"))
      (node (ref "VR36") (pin "P$1") (pinfunction "E_P$1") (pintype "passive"))
    )
    (net (code "93") (name "Net-(VR31-S)") (class "Default")
      (node (ref "R39") (pin "2") (pinfunction "2_2") (pintype "passive"))
      (node (ref "VR31") (pin "P$2") (pinfunction "S_P$2") (pintype "passive"))
    )
    (net (code "94") (name "Net-(VR32-S)") (class "Default")
      (node (ref "R40") (pin "2") (pinfunction "2_2") (pintype "passive"))
      (node (ref "VR32") (pin "P$2") (pinfunction "S_P$2") (pintype "passive"))
    )
    (net (code "95") (name "Net-(VR33-S)") (class "Default")
      (node (ref "R41") (pin "2") (pinfunction "2_2") (pintype "passive"))
      (node (ref "VR33") (pin "P$2") (pinfunction "S_P$2") (pintype "passive"))
    )
    (net (code "96") (name "Net-(VR34-S)") (class "Default")
      (node (ref "R42") (pin "2") (pinfunction "2_2") (pintype "passive"))
      (node (ref "VR34") (pin "P$2") (pinfunction "S_P$2") (pintype "passive"))
    )
    (net (code "97") (name "Net-(VR35-S)") (class "Default")
      (node (ref "R43") (pin "2") (pinfunction "2_2") (pintype "passive"))
      (node (ref "VR35") (pin "P$2") (pinfunction "S_P$2") (pintype "passive"))
    )
    (net (code "98") (name "Net-(VR36-S)") (class "Default")
      (node (ref "R44") (pin "2") (pinfunction "2_2") (pintype "passive"))
      (node (ref "VR36") (pin "P$2") (pinfunction "S_P$2") (pintype "passive"))
    )
    (net (code "99") (name "VCC") (class "Default")
      (node (ref "C11") (pin "1") (pinfunction "1_1") (pintype "passive"))
      (node (ref "C13") (pin "1") (pinfunction "1_1") (pintype "passive"))
      (node (ref "C21") (pin "1") (pinfunction "1_1") (pintype "passive"))
      (node (ref "C22") (pin "1") (pinfunction "1_1") (pintype "passive"))
      (node (ref "C23") (pin "1") (pinfunction "1_1") (pintype "passive"))
      (node (ref "C5") (pin "+") (pinfunction "+_+") (pintype "passive"))
      (node (ref "C7") (pin "1") (pinfunction "1_1") (pintype "passive"))
      (node (ref "C9") (pin "1") (pinfunction "1_1") (pintype "passive"))
      (node (ref "IC2") (pin "OUT") (pinfunction "OUT_OUT") (pintype "passive"))
      (node (ref "IC4") (pin "8") (pinfunction "V+_8") (pintype "power_in"))
      (node (ref "IC5") (pin "8") (pinfunction "V+_8") (pintype "power_in"))
      (node (ref "IC6") (pin "8") (pinfunction "V+_8") (pintype "power_in"))
      (node (ref "IC7") (pin "8") (pinfunction "V+_8") (pintype "power_in"))
      (node (ref "IC8") (pin "8") (pinfunction "V+_8") (pintype "power_in"))
      (node (ref "IC9") (pin "8") (pinfunction "V+_8") (pintype "power_in"))
      (node (ref "L1") (pin "A") (pinfunction "A_A") (pintype "passive"))
      (node (ref "L2") (pin "A") (pinfunction "A_A") (pintype "passive"))
      (node (ref "L3") (pin "A") (pinfunction "A_A") (pintype "passive"))
      (node (ref "L4") (pin "A") (pinfunction "A_A") (pintype "passive"))
      (node (ref "L5") (pin "A") (pinfunction "A_A") (pintype "passive"))
      (node (ref "L6") (pin "A") (pinfunction "A_A") (pintype "passive"))
    )
    (net (code "100") (name "VEE") (class "Default")
      (node (ref "C10") (pin "2") (pinfunction "2_2") (pintype "passive"))
      (node (ref "C12") (pin "2") (pinfunction "2_2") (pintype "passive"))
      (node (ref "C14") (pin "2") (pinfunction "2_2") (pintype "passive"))
      (node (ref "C24") (pin "2") (pinfunction "2_2") (pintype "passive"))
      (node (ref "C25") (pin "2") (pinfunction "2_2") (pintype "passive"))
      (node (ref "C26") (pin "2") (pinfunction "2_2") (pintype "passive"))
      (node (ref "C6") (pin "-") (pinfunction "-_-") (pintype "passive"))
      (node (ref "C8") (pin "2") (pinfunction "2_2") (pintype "passive"))
      (node (ref "IC1") (pin "OUT") (pinfunction "OUT_OUT") (pintype "passive"))
      (node (ref "IC4") (pin "4") (pinfunction "V-_4") (pintype "power_in"))
      (node (ref "IC5") (pin "4") (pinfunction "V-_4") (pintype "power_in"))
      (node (ref "IC6") (pin "4") (pinfunction "V-_4") (pintype "power_in"))
      (node (ref "IC7") (pin "4") (pinfunction "V-_4") (pintype "power_in"))
      (node (ref "IC8") (pin "4") (pinfunction "V-_4") (pintype "power_in"))
      (node (ref "IC9") (pin "4") (pinfunction "V-_4") (pintype "power_in"))
    )
    (net (code "101") (name "unconnected-(IC3-Pad1)") (class "Default")
      (node (ref "IC3") (pin "1") (pinfunction "1_1") (pintype "passive"))
    )
    (net (code "102") (name "unconnected-(IC3-Pad6)") (class "Default")
      (node (ref "IC3") (pin "6") (pinfunction "6_6") (pintype "passive"))
    )
    (net (code "103") (name "unconnected-(O1-PadSN)") (class "Default")
      (node (ref "O1") (pin "SN") (pinfunction "SN_SN") (pintype "passive"))
    )
    (net (code "104") (name "unconnected-(O1-PadT)") (class "Default")
      (node (ref "O1") (pin "T") (pinfunction "T_T") (pintype "passive"))
    )
    (net (code "105") (name "unconnected-(O2-PadSN)") (class "Default")
      (node (ref "O2") (pin "SN") (pinfunction "SN_SN") (pintype "passive"))
    )
    (net (code "106") (name "unconnected-(O3-PadSN)") (class "Default")
      (node (ref "O3") (pin "SN") (pinfunction "SN_SN") (pintype "passive"))
    )
    (net (code "107") (name "unconnected-(O4-PadSN)") (class "Default")
      (node (ref "O4") (pin "SN") (pinfunction "SN_SN") (pintype "passive"))
    )
    (net (code "108") (name "unconnected-(O5-PadSN)") (class "Default")
      (node (ref "O5") (pin "SN") (pinfunction "SN_SN") (pintype "passive"))
    )
    (net (code "109") (name "unconnected-(O6-PadSN)") (class "Default")
      (node (ref "O6") (pin "SN") (pinfunction "SN_SN") (pintype "passive"))
    )
    (net (code "110") (name "unconnected-(POWER-Pad2)") (class "Default")
      (node (ref "POWER") (pin "2") (pinfunction "2_2") (pintype "passive"))
    )
  )
)
